# D-ad_SIL-DIL_V1_1.net
KiCad netlist of a schematic drawn in EAGLE
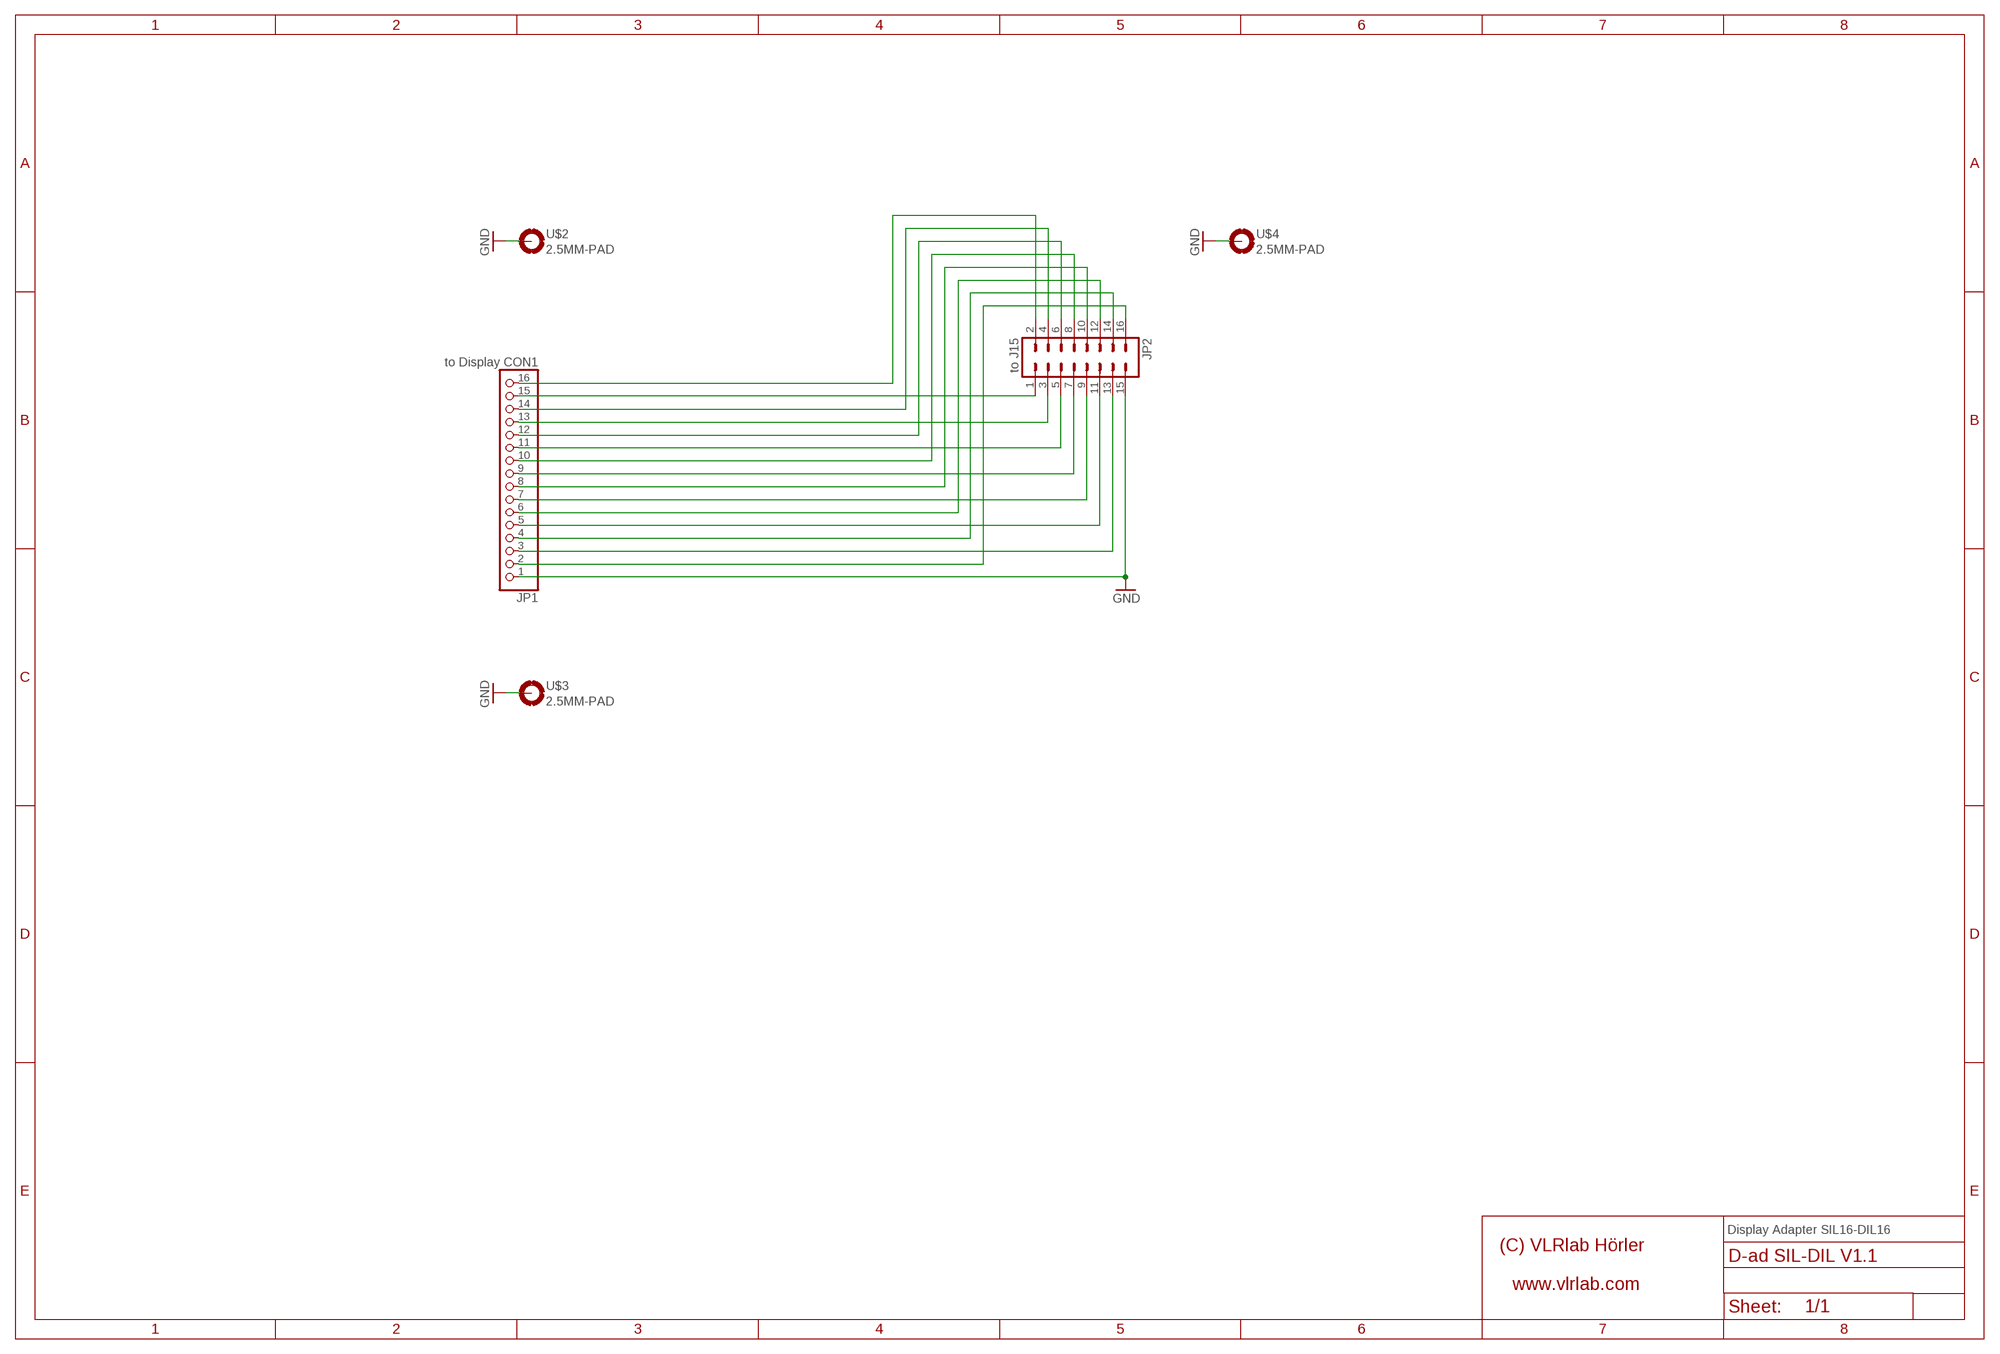
[diagram p0: schematic, sheet 1]

(export (version "E")
  (design (tool "Eeschema 10.0.6"))
  (components
    (comp (ref "JP1")
      (value "to Display CON1")
      (footprint "eagle-import:1X16")
      (libsource (lib "eagle-import") (part "PINHD-1X16"))
    )
    (comp (ref "JP2")
      (value "to J15")
      (footprint "eagle-import:ML16")
      (libsource (lib "eagle-import") (part "ML16"))
    )
    (comp (ref "U$2")
      (value "2.5MM-PAD")
      (footprint "eagle-import:2.5MM-PAD")
      (libsource (lib "eagle-import") (part "2.5MM-PAD"))
    )
    (comp (ref "U$3")
      (value "2.5MM-PAD")
      (footprint "eagle-import:2.5MM-PAD")
      (libsource (lib "eagle-import") (part "2.5MM-PAD"))
    )
    (comp (ref "U$4")
      (value "2.5MM-PAD")
      (footprint "eagle-import:2.5MM-PAD")
      (libsource (lib "eagle-import") (part "2.5MM-PAD"))
    )
  )
  (nets
    (net (code "1") (name "GND") (class "Default")
      (node (ref "JP1") (pin "1") (pinfunction "1_1") (pintype "passive"))
      (node (ref "JP2") (pin "15") (pinfunction "15_15") (pintype "passive"))
      (node (ref "U$2") (pin "B3,2") (pinfunction "MOUNT_B3,2") (pintype "passive"))
      (node (ref "U$3") (pin "B3,2") (pinfunction "MOUNT_B3,2") (pintype "passive"))
      (node (ref "U$4") (pin "B3,2") (pinfunction "MOUNT_B3,2") (pintype "passive"))
    )
    (net (code "2") (name "Net-(JP1-Pad2)") (class "Default")
      (node (ref "JP1") (pin "2") (pinfunction "2_2") (pintype "passive"))
      (node (ref "JP2") (pin "16") (pinfunction "16_16") (pintype "passive"))
    )
    (net (code "3") (name "Net-(JP1-Pad3)") (class "Default")
      (node (ref "JP1") (pin "3") (pinfunction "3_3") (pintype "passive"))
      (node (ref "JP2") (pin "13") (pinfunction "13_13") (pintype "passive"))
    )
    (net (code "4") (name "Net-(JP1-Pad4)") (class "Default")
      (node (ref "JP1") (pin "4") (pinfunction "4_4") (pintype "passive"))
      (node (ref "JP2") (pin "14") (pinfunction "14_14") (pintype "passive"))
    )
    (net (code "5") (name "Net-(JP1-Pad5)") (class "Default")
      (node (ref "JP1") (pin "5") (pinfunction "5_5") (pintype "passive"))
      (node (ref "JP2") (pin "11") (pinfunction "11_11") (pintype "passive"))
    )
    (net (code "6") (name "Net-(JP1-Pad6)") (class "Default")
      (node (ref "JP1") (pin "6") (pinfunction "6_6") (pintype "passive"))
      (node (ref "JP2") (pin "12") (pinfunction "12_12") (pintype "passive"))
    )
    (net (code "7") (name "Net-(JP1-Pad7)") (class "Default")
      (node (ref "JP1") (pin "7") (pinfunction "7_7") (pintype "passive"))
      (node (ref "JP2") (pin "9") (pinfunction "9_9") (pintype "passive"))
    )
    (net (code "8") (name "Net-(JP1-Pad8)") (class "Default")
      (node (ref "JP1") (pin "8") (pinfunction "8_8") (pintype "passive"))
      (node (ref "JP2") (pin "10") (pinfunction "10_10") (pintype "passive"))
    )
    (net (code "9") (name "Net-(JP1-Pad9)") (class "Default")
      (node (ref "JP1") (pin "9") (pinfunction "9_9") (pintype "passive"))
      (node (ref "JP2") (pin "7") (pinfunction "7_7") (pintype "passive"))
    )
    (net (code "10") (name "Net-(JP1-Pad10)") (class "Default")
      (node (ref "JP1") (pin "10") (pinfunction "10_10") (pintype "passive"))
      (node (ref "JP2") (pin "8") (pinfunction "8_8") (pintype "passive"))
    )
    (net (code "11") (name "Net-(JP1-Pad11)") (class "Default")
      (node (ref "JP1") (pin "11") (pinfunction "11_11") (pintype "passive"))
      (node (ref "JP2") (pin "5") (pinfunction "5_5") (pintype "passive"))
    )
    (net (code "12") (name "Net-(JP1-Pad12)") (class "Default")
      (node (ref "JP1") (pin "12") (pinfunction "12_12") (pintype "passive"))
      (node (ref "JP2") (pin "6") (pinfunction "6_6") (pintype "passive"))
    )
    (net (code "13") (name "Net-(JP1-Pad13)") (class "Default")
      (node (ref "JP1") (pin "13") (pinfunction "13_13") (pintype "passive"))
      (node (ref "JP2") (pin "3") (pinfunction "3_3") (pintype "passive"))
    )
    (net (code "14") (name "Net-(JP1-Pad14)") (class "Default")
      (node (ref "JP1") (pin "14") (pinfunction "14_14") (pintype "passive"))
      (node (ref "JP2") (pin "4") (pinfunction "4_4") (pintype "passive"))
    )
    (net (code "15") (name "Net-(JP1-Pad15)") (class "Default")
      (node (ref "JP1") (pin "15") (pinfunction "15_15") (pintype "passive"))
      (node (ref "JP2") (pin "1") (pinfunction "1_1") (pintype "passive"))
    )
    (net (code "16") (name "Net-(JP1-Pad16)") (class "Default")
      (node (ref "JP1") (pin "16") (pinfunction "16_16") (pintype "passive"))
      (node (ref "JP2") (pin "2") (pinfunction "2_2") (pintype "passive"))
    )
  )
)
